# KH-TYPE-C-16P.net
KiCad netlist of a schematic drawn in Altium Designer
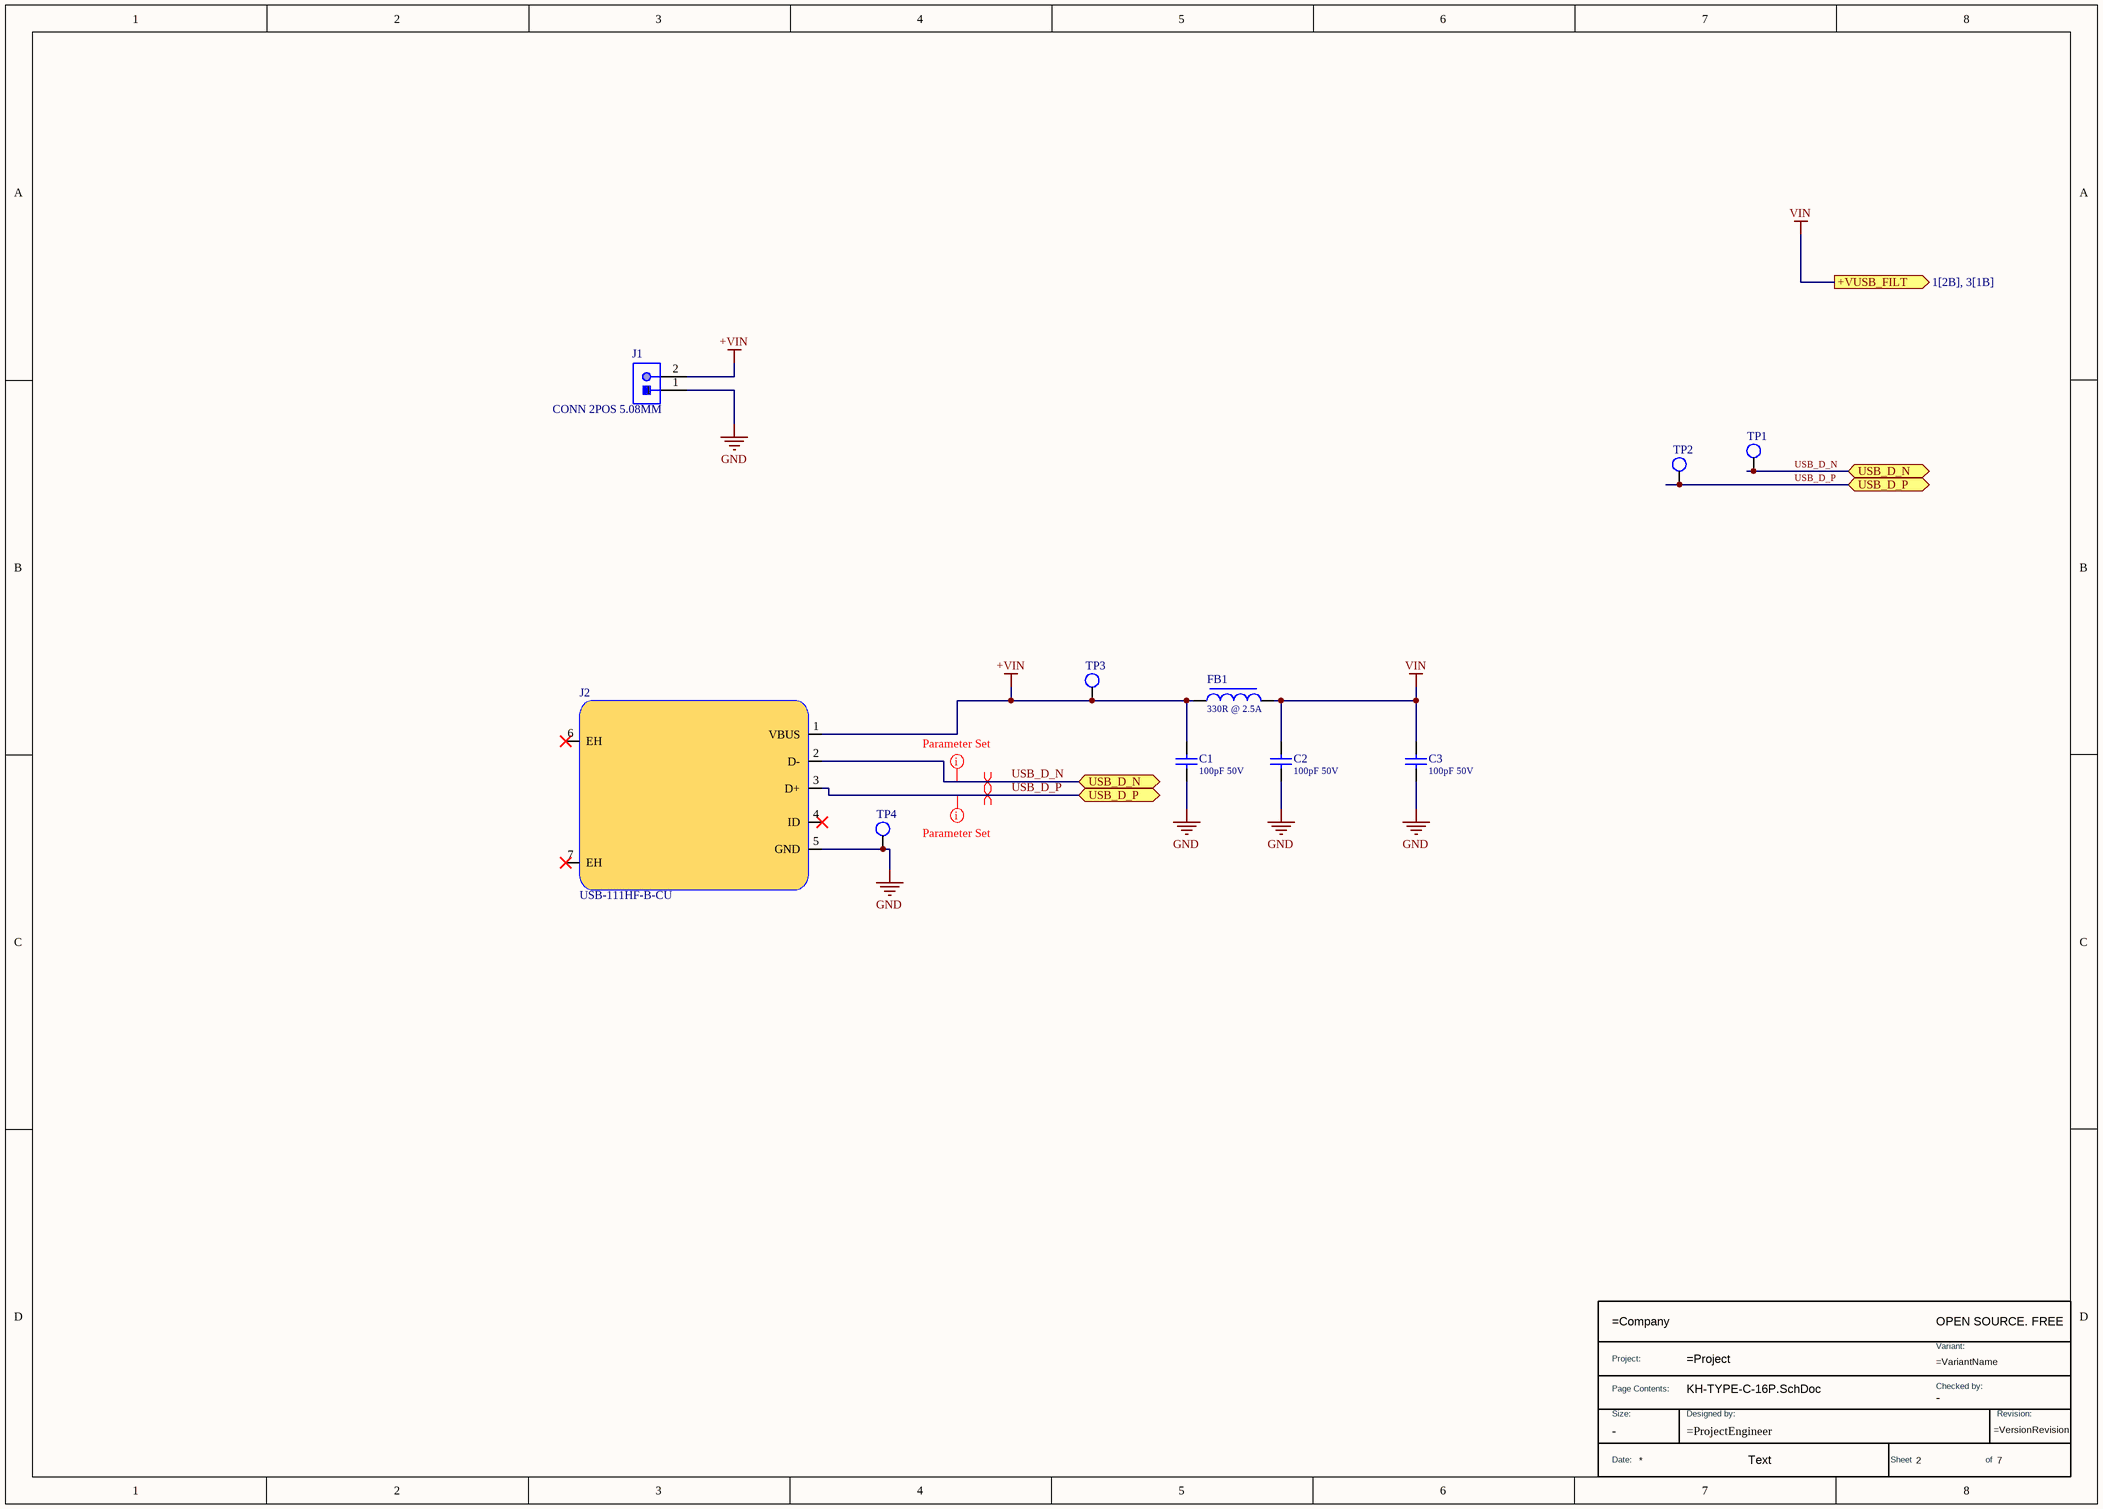
[diagram p0: KH-TYPE-C-16P.SchDoc]

(export (version "E")
  (design (tool "Eeschema 10.0.6"))
  (components
    (comp (ref "C1")
      (value "CC0805JRNPO9BN101")
      (footprint "CAP_0805")
      (description "CAP CER 100PF 50V C0G/NPO 0805")
      (fields (field (name "MANUFACTURER") "YAGEO") (field (name "VALOR") "100pF 50V"))
      (libsource (lib "OBDH_Ed02") (part "CC0805JRNPO9BN101"))
    )
    (comp (ref "C2")
      (value "CC0805JRNPO9BN101")
      (footprint "CAP_0805")
      (description "CAP CER 100PF 50V C0G/NPO 0805")
      (fields (field (name "MANUFACTURER") "YAGEO") (field (name "VALOR") "100pF 50V"))
      (libsource (lib "OBDH_Ed02") (part "CC0805JRNPO9BN101"))
    )
    (comp (ref "C3")
      (value "CC0805JRNPO9BN101")
      (footprint "CAP_0805")
      (description "CAP CER 100PF 50V C0G/NPO 0805")
      (fields (field (name "MANUFACTURER") "YAGEO") (field (name "VALOR") "100pF 50V"))
      (libsource (lib "OBDH_Ed02") (part "CC0805JRNPO9BN101"))
    )
    (comp (ref "FB1")
      (value "MPZ2012S331AT000")
      (footprint "IND_0805")
      (description "FERRITE BEAD 330 OHM 0805 1LN")
      (fields (field (name "MANUFACTURER") "TDK Corporation") (field (name "VALOR") "330R @ 2.5A"))
      (libsource (lib "OBDH_Ed02") (part "MPZ2012S331AT000"))
    )
    (comp (ref "J1")
      (value "796638-2")
      (footprint "CONN TERM BLOCK 2POS 5.08MM")
      (description "CONN TERM BLOCK HDR 2POS 90DEG 5.08MM")
      (fields
        (field (name "MANUFACTURER") "TE Connectivity AMP Connectors")
        (field (name "VALOR") "CONN 2POS 5.08MM")
      )
      (libsource (lib "OBDH_Ed02") (part "796638-2"))
    )
    (comp (ref "J2")
      (value "USB-111HF-B-CU")
      (footprint "USB-111HF-B-CU")
      (description "Female 5 Micro-B Surface Mount SMD USB Connectors ROHS")
      (libsource (lib "OBDH_Ed02") (part "USB-111HF-B-CU"))
    )
    (comp (ref "TP1")
      (value "TEST_POINT_1.5MM")
      (footprint "TESTPOINT_1.5MM")
      (description "TEST_POINT")
      (libsource (lib "OBDH_Ed02") (part "TEST_POINT_1.5MM"))
    )
    (comp (ref "TP2")
      (value "TEST_POINT_1.5MM")
      (footprint "TESTPOINT_1.5MM")
      (description "TEST_POINT")
      (libsource (lib "OBDH_Ed02") (part "TEST_POINT_1.5MM"))
    )
    (comp (ref "TP3")
      (value "TEST_POINT_1.5MM")
      (footprint "TESTPOINT_1.5MM")
      (description "TEST_POINT")
      (libsource (lib "OBDH_Ed02") (part "TEST_POINT_1.5MM"))
    )
    (comp (ref "TP4")
      (value "TEST_POINT_1.5MM")
      (footprint "TESTPOINT_1.5MM")
      (description "TEST_POINT")
      (libsource (lib "OBDH_Ed02") (part "TEST_POINT_1.5MM"))
    )
  )
  (nets
    (net (code "1") (name "+VIN") (class "Default")
      (node (ref "C1") (pin "2") (pinfunction "2_2") (pintype "passive"))
      (node (ref "FB1") (pin "1") (pinfunction "1_1") (pintype "passive"))
      (node (ref "J1") (pin "2") (pinfunction "2_2") (pintype "passive"))
      (node (ref "J2") (pin "1") (pinfunction "VBUS_1") (pintype "passive"))
      (node (ref "TP3") (pin "1") (pinfunction "1_1") (pintype "passive"))
    )
    (net (code "2") (name "/USB_D_N") (class "Default")
      (node (ref "J2") (pin "2") (pinfunction "D-_2") (pintype "passive"))
      (node (ref "TP1") (pin "1") (pinfunction "1_1") (pintype "passive"))
    )
    (net (code "3") (name "/USB_D_P") (class "Default")
      (node (ref "J2") (pin "3") (pinfunction "D+_3") (pintype "passive"))
      (node (ref "TP2") (pin "1") (pinfunction "1_1") (pintype "passive"))
    )
    (net (code "4") (name "GND") (class "Default")
      (node (ref "C1") (pin "1") (pinfunction "1_1") (pintype "passive"))
      (node (ref "C2") (pin "1") (pinfunction "1_1") (pintype "passive"))
      (node (ref "C3") (pin "1") (pinfunction "1_1") (pintype "passive"))
      (node (ref "J1") (pin "1") (pinfunction "1_1") (pintype "passive"))
      (node (ref "J2") (pin "5") (pinfunction "GND_5") (pintype "passive"))
      (node (ref "TP4") (pin "1") (pinfunction "1_1") (pintype "passive"))
    )
    (net (code "5") (name "VIN") (class "Default")
      (node (ref "C2") (pin "2") (pinfunction "2_2") (pintype "passive"))
      (node (ref "C3") (pin "2") (pinfunction "2_2") (pintype "passive"))
      (node (ref "FB1") (pin "2") (pinfunction "2_2") (pintype "passive"))
    )
    (net (code "6") (name "unconnected-(J2-EH-Pad6)") (class "Default")
      (node (ref "J2") (pin "6") (pinfunction "EH_6") (pintype "passive+no_connect"))
    )
    (net (code "7") (name "unconnected-(J2-EH-Pad7)") (class "Default")
      (node (ref "J2") (pin "7") (pinfunction "EH_7") (pintype "passive+no_connect"))
    )
    (net (code "8") (name "unconnected-(J2-ID-Pad4)") (class "Default")
      (node (ref "J2") (pin "4") (pinfunction "ID_4") (pintype "passive+no_connect"))
    )
  )
)
